# Clock_Distribution.net
KiCad netlist of a schematic drawn in Altium Designer
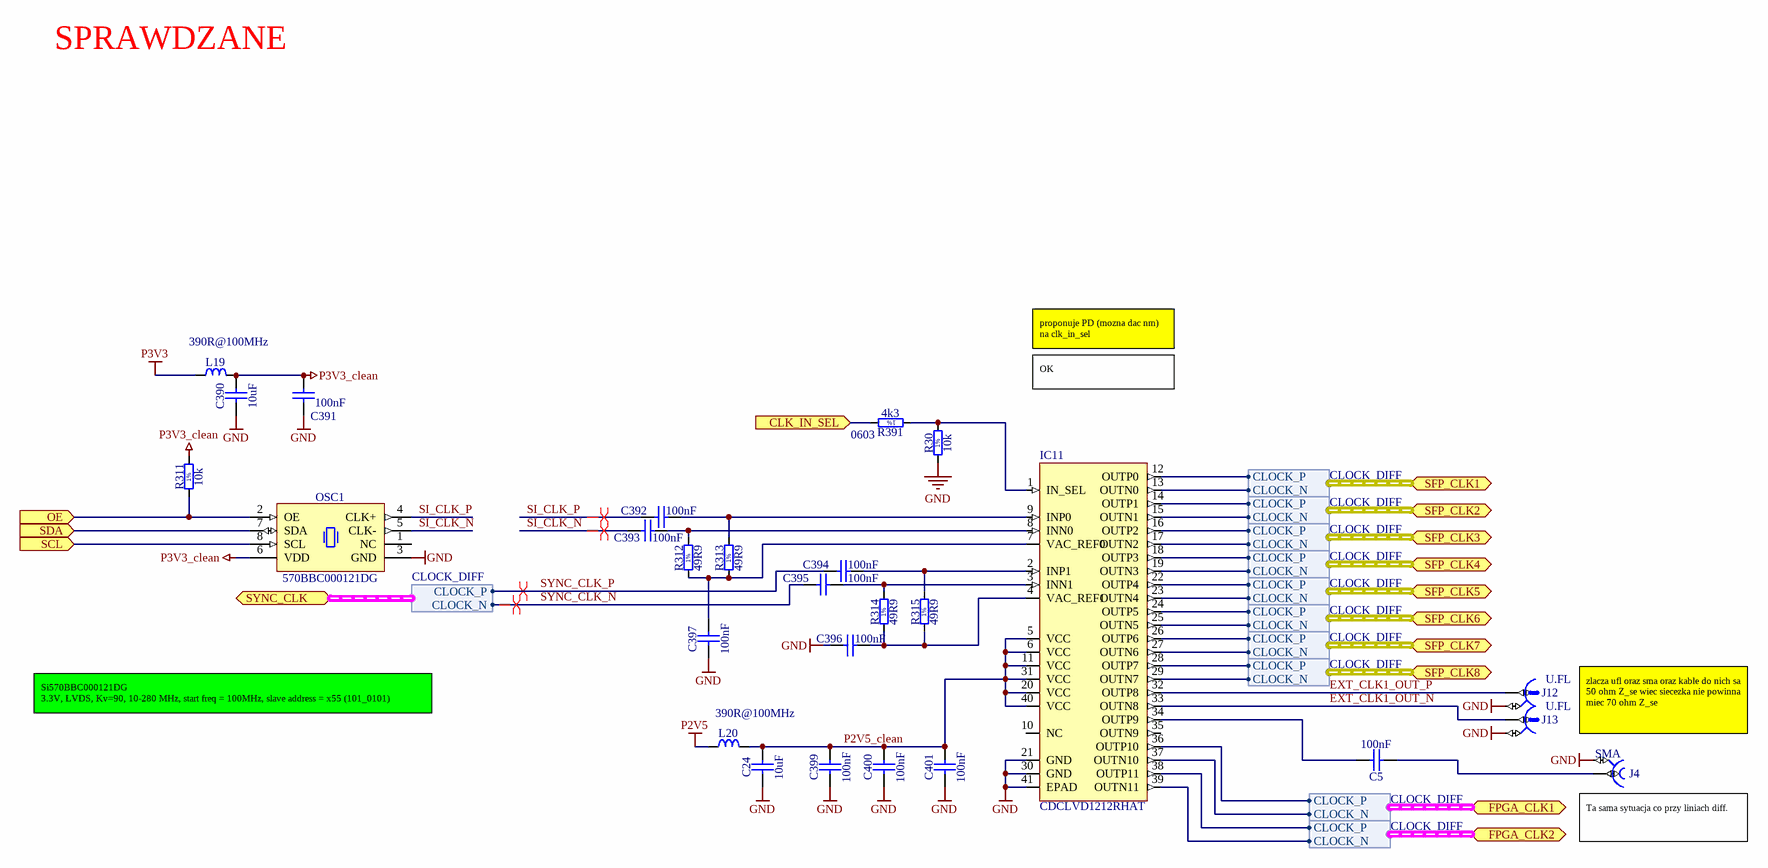
[diagram p0: Clock_Distribution.SchDoc]

(export (version "E")
  (design (tool "Eeschema 10.0.6"))
  (components
    (comp (ref "C5")
      (value "100nF")
      (footprint "CAPC1005X55N")
      (description "Non-polarised capacitor")
      (fields
        (field (name "PART NUMBER") "CC0402_100NF_16V_10%_X7R")
        (field (name "VOLTAGE") "16V")
        (field (name "AUTHOR") "CERN DEM JLC")
      )
      (libsource (lib "Capacitors") (part "Capacitor - non polarized"))
    )
    (comp (ref "C24")
      (value "10uF")
      (footprint "CAPC2012X135N")
      (description "Non-polarised capacitor")
      (fields
        (field (name "PART NUMBER") "CC0805_10UF_10V_10%_X7R")
        (field (name "VOLTAGE") "10V")
        (field (name "AUTHOR") "CERN DEM JLC")
      )
      (libsource (lib "Capacitors") (part "Capacitor - non polarized"))
    )
    (comp (ref "C390")
      (value "10uF")
      (footprint "CAPC2012X135N")
      (description "Non-polarised capacitor")
      (fields
        (field (name "PART NUMBER") "CC0805_10UF_10V_10%_X7R")
        (field (name "VOLTAGE") "10V")
        (field (name "AUTHOR") "CERN DEM JLC")
      )
      (libsource (lib "Capacitors") (part "Capacitor - non polarized"))
    )
    (comp (ref "C391")
      (value "100nF")
      (footprint "CAPC0603X33N")
      (description "Non-polarised capacitor")
      (fields
        (field (name "PART NUMBER") "CC0201_100NF_6.3V_10%_X5R")
        (field (name "VOLTAGE") "6.3V")
        (field (name "AUTHOR") "CERN DEM JLC")
      )
      (libsource (lib "Capacitors") (part "Capacitor - non polarized"))
    )
    (comp (ref "C392")
      (value "100nF")
      (footprint "CAPC0603X33N")
      (description "Non-polarised capacitor")
      (fields
        (field (name "PART NUMBER") "CC0201_100NF_6.3V_10%_X5R")
        (field (name "VOLTAGE") "6.3V")
        (field (name "AUTHOR") "CERN DEM JLC")
      )
      (libsource (lib "Capacitors") (part "Capacitor - non polarized"))
    )
    (comp (ref "C393")
      (value "100nF")
      (footprint "CAPC0603X33N")
      (description "Non-polarised capacitor")
      (fields
        (field (name "PART NUMBER") "CC0201_100NF_6.3V_10%_X5R")
        (field (name "VOLTAGE") "6.3V")
        (field (name "AUTHOR") "CERN DEM JLC")
      )
      (libsource (lib "Capacitors") (part "Capacitor - non polarized"))
    )
    (comp (ref "C394")
      (value "100nF")
      (footprint "CAPC0603X33N")
      (description "Non-polarised capacitor")
      (fields
        (field (name "PART NUMBER") "CC0201_100NF_6.3V_10%_X5R")
        (field (name "VOLTAGE") "6.3V")
        (field (name "AUTHOR") "CERN DEM JLC")
      )
      (libsource (lib "Capacitors") (part "Capacitor - non polarized"))
    )
    (comp (ref "C395")
      (value "100nF")
      (footprint "CAPC0603X33N")
      (description "Non-polarised capacitor")
      (fields
        (field (name "PART NUMBER") "CC0201_100NF_6.3V_10%_X5R")
        (field (name "VOLTAGE") "6.3V")
        (field (name "AUTHOR") "CERN DEM JLC")
      )
      (libsource (lib "Capacitors") (part "Capacitor - non polarized"))
    )
    (comp (ref "C396")
      (value "100nF")
      (footprint "CAPC0603X33N")
      (description "Non-polarised capacitor")
      (fields
        (field (name "PART NUMBER") "CC0201_100NF_6.3V_10%_X5R")
        (field (name "VOLTAGE") "6.3V")
        (field (name "AUTHOR") "CERN DEM JLC")
      )
      (libsource (lib "Capacitors") (part "Capacitor - non polarized"))
    )
    (comp (ref "C397")
      (value "100nF")
      (footprint "CAPC0603X33N")
      (description "Non-polarised capacitor")
      (fields
        (field (name "PART NUMBER") "CC0201_100NF_6.3V_10%_X5R")
        (field (name "VOLTAGE") "6.3V")
        (field (name "AUTHOR") "CERN DEM JLC")
      )
      (libsource (lib "Capacitors") (part "Capacitor - non polarized"))
    )
    (comp (ref "C399")
      (value "100nF")
      (footprint "CAPC0603X33N")
      (description "Non-polarised capacitor")
      (fields
        (field (name "PART NUMBER") "CC0201_100NF_6.3V_10%_X5R")
        (field (name "VOLTAGE") "6.3V")
        (field (name "AUTHOR") "CERN DEM JLC")
      )
      (libsource (lib "Capacitors") (part "Capacitor - non polarized"))
    )
    (comp (ref "C400")
      (value "100nF")
      (footprint "CAPC0603X33N")
      (description "Non-polarised capacitor")
      (fields
        (field (name "PART NUMBER") "CC0201_100NF_6.3V_10%_X5R")
        (field (name "VOLTAGE") "6.3V")
        (field (name "AUTHOR") "CERN DEM JLC")
      )
      (libsource (lib "Capacitors") (part "Capacitor - non polarized"))
    )
    (comp (ref "C401")
      (value "100nF")
      (footprint "CAPC0603X33N")
      (description "Non-polarised capacitor")
      (fields
        (field (name "PART NUMBER") "CC0201_100NF_6.3V_10%_X5R")
        (field (name "VOLTAGE") "6.3V")
        (field (name "AUTHOR") "CERN DEM JLC")
      )
      (libsource (lib "Capacitors") (part "Capacitor - non polarized"))
    )
    (comp (ref "IC11")
      (value "CDCLVD1212RHAT")
      (footprint "QFN50P600-40")
      (description "Low Jitter, 2-Input Selectable 1:12 Universal-to-LVDS Buffer")
      (libsource (lib "LIBRARY_SCH") (part "CLOCK_CDCLVD1212"))
    )
    (comp (ref "J4")
      (value "SMA")
      (footprint "HUBER-SUHNER_85 SMA-50-0-101/111 NE")
      (fields
        (field (name "PART NUMBER") "HUBER-SUHNER_85_SMA-50-0-101/111_NE")
        (field (name "MANUFACTURER") "HUBER+SUHNER")
        (field (name "MANUFACTURER PART NUMBER") "85_SMA-50-0-101/111_NE")
        (field (name "AUTHOR") "CERN DEM JLC")
      )
      (libsource (lib "Connectors") (part "Coax_1Female_1Shield"))
    )
    (comp (ref "J12")
      (value "U.FL")
      (footprint "HIROSE_U.FL-R-SMT-1(10)")
      (fields
        (field (name "PART NUMBER") "HIROSE_U.FL-R-SMT-1(10)")
        (field (name "MANUFACTURER") "HIROSE (HRS)")
        (field (name "MANUFACTURER PART NUMBER") "U.FL-R-SMT-1(10)")
        (field (name "AUTHOR") "CERN DEM JLC")
      )
      (libsource (lib "Connectors") (part "Coax_1Male_1Shield"))
    )
    (comp (ref "J13")
      (value "U.FL")
      (footprint "HIROSE_U.FL-R-SMT-1(10)")
      (fields
        (field (name "PART NUMBER") "HIROSE_U.FL-R-SMT-1(10)")
        (field (name "MANUFACTURER") "HIROSE (HRS)")
        (field (name "MANUFACTURER PART NUMBER") "U.FL-R-SMT-1(10)")
        (field (name "AUTHOR") "CERN DEM JLC")
      )
      (libsource (lib "Connectors") (part "Coax_1Male_1Shield"))
    )
    (comp (ref "L19")
      (value "390R@100MHz")
      (footprint "INDC1608X95N")
      (description "Inductor")
      (fields
        (field (name "PART NUMBER") "IND0603_TDK_MPZ1608R391A")
        (field (name "POWER") "1.2A")
        (field (name "AUTHOR") "CERN DEM JLC")
      )
      (libsource (lib "Inductors & Transformers") (part "Inductor"))
    )
    (comp (ref "L20")
      (value "390R@100MHz")
      (footprint "INDC1608X95N")
      (description "Inductor")
      (fields
        (field (name "PART NUMBER") "IND0603_TDK_MPZ1608R391A")
        (field (name "POWER") "1.2A")
        (field (name "AUTHOR") "CERN DEM JLC")
      )
      (libsource (lib "Inductors & Transformers") (part "Inductor"))
    )
    (comp (ref "OSC1")
      (value "570BBC000121DG")
      (footprint "OSC_SILICON-LAB_SI570")
      (description "Any-Rate I2C Programmable XO Oscillator Si570 Serie")
      (fields
        (field (name "PART NUMBER") "OSC_10-280MHZ_SILICON-LAB_Si570BBC000121DG")
        (field (name "MANUFACTURER") "SILICON LABS")
        (field (name "AUTHOR") "CERN DEM JLC")
      )
      (libsource (lib "ICs And Semiconductors") (part "Oscillator SILICON-LAB_Si570"))
    )
    (comp (ref "R30")
      (value "10k")
      (footprint "RESC1005X40N")
      (description "Resistor - 1%")
      (fields
        (field (name "PART NUMBER") "R0402_10K_1%_0.0625W_100PPM")
        (field (name "POWER") "0.0625W")
        (field (name "AUTHOR") "CERN DEM JLC")
      )
      (libsource (lib "Resistors") (part "Resistor - 1%"))
    )
    (comp (ref "R311")
      (value "10k")
      (footprint "RESC1005X40N")
      (description "Resistor - 1%")
      (fields
        (field (name "PART NUMBER") "R0402_10K_1%_0.0625W_100PPM")
        (field (name "POWER") "0.0625W")
        (field (name "AUTHOR") "CERN DEM JLC")
      )
      (libsource (lib "Resistors") (part "Resistor - 1%"))
    )
    (comp (ref "R312")
      (value "49R9")
      (footprint "RESC1005X40N")
      (description "Resistor - 1%")
      (fields
        (field (name "PART NUMBER") "R0402_49R9_1%_0.0625W_100PPM")
        (field (name "POWER") "0.0625W")
        (field (name "AUTHOR") "CERN DEM JLC")
      )
      (libsource (lib "Resistors") (part "Resistor - 1%"))
    )
    (comp (ref "R313")
      (value "49R9")
      (footprint "RESC1005X40N")
      (description "Resistor - 1%")
      (fields
        (field (name "PART NUMBER") "R0402_49R9_1%_0.0625W_100PPM")
        (field (name "POWER") "0.0625W")
        (field (name "AUTHOR") "CERN DEM JLC")
      )
      (libsource (lib "Resistors") (part "Resistor - 1%"))
    )
    (comp (ref "R314")
      (value "49R9")
      (footprint "RESC1005X40N")
      (description "Resistor - 1%")
      (fields
        (field (name "PART NUMBER") "R0402_49R9_1%_0.0625W_100PPM")
        (field (name "POWER") "0.0625W")
        (field (name "AUTHOR") "CERN DEM JLC")
      )
      (libsource (lib "Resistors") (part "Resistor - 1%"))
    )
    (comp (ref "R315")
      (value "49R9")
      (footprint "RESC1005X40N")
      (description "Resistor - 1%")
      (fields
        (field (name "PART NUMBER") "R0402_49R9_1%_0.0625W_100PPM")
        (field (name "POWER") "0.0625W")
        (field (name "AUTHOR") "CERN DEM JLC")
      )
      (libsource (lib "Resistors") (part "Resistor - 1%"))
    )
    (comp (ref "R391")
      (value "4k3")
      (footprint "RESC1608X55N")
      (description "Resistor - 1%")
      (fields
        (field (name "PART NUMBER") "R0603_4K3_1%_0.1W_100PPM")
        (field (name "POWER") "0.1W")
        (field (name "CASE") "0603")
        (field (name "AUTHOR") "CERN DEM JLC")
      )
      (libsource (lib "Resistors") (part "Resistor - 1%"))
    )
  )
  (nets
    (net (code "3") (name "/CLK_IN_SEL") (class "Default")
      (node (ref "R391") (pin "2") (pinfunction "2_2") (pintype "passive"))
    )
    (net (code "4") (name "/EXT_CLK1_OUT_N") (class "Default")
      (node (ref "IC11") (pin "33") (pinfunction "OUTN8_33") (pintype "output"))
      (node (ref "J13") (pin "1") (pinfunction "1_1") (pintype "bidirectional"))
    )
    (net (code "5") (name "/EXT_CLK1_OUT_P") (class "Default")
      (node (ref "IC11") (pin "32") (pinfunction "OUTP8_32") (pintype "output"))
      (node (ref "J12") (pin "1") (pinfunction "1_1") (pintype "bidirectional"))
    )
    (net (code "6") (name "/OE") (class "Default")
      (node (ref "OSC1") (pin "2") (pinfunction "OE_2") (pintype "input"))
      (node (ref "R311") (pin "1") (pinfunction "1_1") (pintype "passive"))
    )
    (net (code "7") (name "/P2V5_clean") (class "Default")
      (node (ref "C24") (pin "2") (pinfunction "2_2") (pintype "passive"))
      (node (ref "C399") (pin "2") (pinfunction "2_2") (pintype "passive"))
      (node (ref "C400") (pin "2") (pinfunction "2_2") (pintype "passive"))
      (node (ref "C401") (pin "2") (pinfunction "2_2") (pintype "passive"))
      (node (ref "IC11") (pin "11") (pinfunction "VCC_11") (pintype "power_in"))
      (node (ref "IC11") (pin "20") (pinfunction "VCC_20") (pintype "power_in"))
      (node (ref "IC11") (pin "31") (pinfunction "VCC_31") (pintype "power_in"))
      (node (ref "IC11") (pin "40") (pinfunction "VCC_40") (pintype "power_in"))
      (node (ref "IC11") (pin "5") (pinfunction "VCC_5") (pintype "power_in"))
      (node (ref "IC11") (pin "6") (pinfunction "VCC_6") (pintype "power_in"))
      (node (ref "L20") (pin "2") (pinfunction "2_2") (pintype "passive"))
    )
    (net (code "8") (name "/SCL") (class "Default")
      (node (ref "OSC1") (pin "8") (pinfunction "SCL_8") (pintype "input"))
    )
    (net (code "9") (name "/SDA") (class "Default")
      (node (ref "OSC1") (pin "7") (pinfunction "SDA_7") (pintype "bidirectional"))
    )
    (net (code "11") (name "/SI_CLK_N") (class "Default")
      (node (ref "C393") (pin "2") (pinfunction "2_2") (pintype "passive"))
      (node (ref "OSC1") (pin "5") (pinfunction "CLK-_5") (pintype "output"))
    )
    (net (code "12") (name "/SI_CLK_P") (class "Default")
      (node (ref "C392") (pin "2") (pinfunction "2_2") (pintype "passive"))
      (node (ref "OSC1") (pin "4") (pinfunction "CLK+_4") (pintype "output"))
    )
    (net (code "13") (name "/SYNC_CLK_N") (class "Default")
      (node (ref "C395") (pin "2") (pinfunction "2_2") (pintype "passive"))
    )
    (net (code "14") (name "/SYNC_CLK_P") (class "Default")
      (node (ref "C394") (pin "2") (pinfunction "2_2") (pintype "passive"))
    )
    (net (code "16") (name "GND") (class "Default")
      (node (ref "C24") (pin "1") (pinfunction "1_1") (pintype "passive"))
      (node (ref "C390") (pin "1") (pinfunction "1_1") (pintype "passive"))
      (node (ref "C391") (pin "1") (pinfunction "1_1") (pintype "passive"))
      (node (ref "C396") (pin "1") (pinfunction "1_1") (pintype "passive"))
      (node (ref "C397") (pin "1") (pinfunction "1_1") (pintype "passive"))
      (node (ref "C399") (pin "1") (pinfunction "1_1") (pintype "passive"))
      (node (ref "C400") (pin "1") (pinfunction "1_1") (pintype "passive"))
      (node (ref "C401") (pin "1") (pinfunction "1_1") (pintype "passive"))
      (node (ref "IC11") (pin "21") (pinfunction "GND_21") (pintype "power_in"))
      (node (ref "IC11") (pin "30") (pinfunction "GND_30") (pintype "power_in"))
      (node (ref "IC11") (pin "41") (pinfunction "EPAD_41") (pintype "power_in"))
      (node (ref "J12") (pin "2") (pinfunction "2_2") (pintype "bidirectional"))
      (node (ref "J13") (pin "2") (pinfunction "2_2") (pintype "bidirectional"))
      (node (ref "J4") (pin "2") (pinfunction "2_2") (pintype "bidirectional"))
      (node (ref "OSC1") (pin "3") (pinfunction "GND_3") (pintype "power_in"))
      (node (ref "R30") (pin "1") (pinfunction "1_1") (pintype "passive"))
    )
    (net (code "17") (name "Net-(C5-Pad2)") (class "Default")
      (node (ref "C5") (pin "2") (pinfunction "2_2") (pintype "passive"))
      (node (ref "J4") (pin "1") (pinfunction "1_1") (pintype "bidirectional"))
    )
    (net (code "18") (name "Net-(IC11-INN0)") (class "Default")
      (node (ref "C393") (pin "1") (pinfunction "1_1") (pintype "passive"))
      (node (ref "IC11") (pin "8") (pinfunction "INN0_8") (pintype "input"))
      (node (ref "R312") (pin "2") (pinfunction "2_2") (pintype "passive"))
    )
    (net (code "19") (name "Net-(IC11-INN1)") (class "Default")
      (node (ref "C395") (pin "1") (pinfunction "1_1") (pintype "passive"))
      (node (ref "IC11") (pin "3") (pinfunction "INN1_3") (pintype "input"))
      (node (ref "R314") (pin "2") (pinfunction "2_2") (pintype "passive"))
    )
    (net (code "20") (name "Net-(IC11-INP0)") (class "Default")
      (node (ref "C392") (pin "1") (pinfunction "1_1") (pintype "passive"))
      (node (ref "IC11") (pin "9") (pinfunction "INP0_9") (pintype "input"))
      (node (ref "R313") (pin "2") (pinfunction "2_2") (pintype "passive"))
    )
    (net (code "21") (name "Net-(IC11-INP1)") (class "Default")
      (node (ref "C394") (pin "1") (pinfunction "1_1") (pintype "passive"))
      (node (ref "IC11") (pin "2") (pinfunction "INP1_2") (pintype "input"))
      (node (ref "R315") (pin "2") (pinfunction "2_2") (pintype "passive"))
    )
    (net (code "22") (name "Net-(IC11-IN_SEL)") (class "Default")
      (node (ref "IC11") (pin "1") (pinfunction "IN_SEL_1") (pintype "input"))
      (node (ref "R30") (pin "2") (pinfunction "2_2") (pintype "passive"))
      (node (ref "R391") (pin "1") (pinfunction "1_1") (pintype "passive"))
    )
    (net (code "23") (name "Net-(IC11-OUTP9)") (class "Default")
      (node (ref "C5") (pin "1") (pinfunction "1_1") (pintype "passive"))
      (node (ref "IC11") (pin "34") (pinfunction "OUTP9_34") (pintype "output"))
    )
    (net (code "24") (name "Net-(IC11-VAC_REF0)") (class "Default")
      (node (ref "C397") (pin "2") (pinfunction "2_2") (pintype "passive"))
      (node (ref "IC11") (pin "7") (pinfunction "VAC_REF0_7") (pintype "power_in"))
      (node (ref "R312") (pin "1") (pinfunction "1_1") (pintype "passive"))
      (node (ref "R313") (pin "1") (pinfunction "1_1") (pintype "passive"))
    )
    (net (code "25") (name "Net-(IC11-VAC_REF1)") (class "Default")
      (node (ref "C396") (pin "2") (pinfunction "2_2") (pintype "passive"))
      (node (ref "IC11") (pin "4") (pinfunction "VAC_REF1_4") (pintype "power_in"))
      (node (ref "R314") (pin "1") (pinfunction "1_1") (pintype "passive"))
      (node (ref "R315") (pin "1") (pinfunction "1_1") (pintype "passive"))
    )
    (net (code "26") (name "P2V5") (class "Default")
      (node (ref "L20") (pin "1") (pinfunction "1_1") (pintype "passive"))
    )
    (net (code "27") (name "P3V3") (class "Default")
      (node (ref "L19") (pin "1") (pinfunction "1_1") (pintype "passive"))
    )
    (net (code "28") (name "P3V3_clean") (class "Default")
      (node (ref "C390") (pin "2") (pinfunction "2_2") (pintype "passive"))
      (node (ref "C391") (pin "2") (pinfunction "2_2") (pintype "passive"))
      (node (ref "L19") (pin "2") (pinfunction "2_2") (pintype "passive"))
      (node (ref "OSC1") (pin "6") (pinfunction "VDD_6") (pintype "power_in"))
      (node (ref "R311") (pin "2") (pinfunction "2_2") (pintype "passive"))
    )
    (net (code "29") (name "unconnected-(IC11-NC-Pad10)") (class "Default")
      (node (ref "IC11") (pin "10") (pinfunction "NC_10") (pintype "passive"))
    )
    (net (code "30") (name "unconnected-(IC11-OUTN0-Pad13)") (class "Default")
      (node (ref "IC11") (pin "13") (pinfunction "OUTN0_13") (pintype "output"))
    )
    (net (code "31") (name "unconnected-(IC11-OUTN1-Pad15)") (class "Default")
      (node (ref "IC11") (pin "15") (pinfunction "OUTN1_15") (pintype "output"))
    )
    (net (code "32") (name "unconnected-(IC11-OUTN2-Pad17)") (class "Default")
      (node (ref "IC11") (pin "17") (pinfunction "OUTN2_17") (pintype "output"))
    )
    (net (code "33") (name "unconnected-(IC11-OUTN3-Pad19)") (class "Default")
      (node (ref "IC11") (pin "19") (pinfunction "OUTN3_19") (pintype "output"))
    )
    (net (code "34") (name "unconnected-(IC11-OUTN4-Pad23)") (class "Default")
      (node (ref "IC11") (pin "23") (pinfunction "OUTN4_23") (pintype "output"))
    )
    (net (code "35") (name "unconnected-(IC11-OUTN5-Pad25)") (class "Default")
      (node (ref "IC11") (pin "25") (pinfunction "OUTN5_25") (pintype "output"))
    )
    (net (code "36") (name "unconnected-(IC11-OUTN6-Pad27)") (class "Default")
      (node (ref "IC11") (pin "27") (pinfunction "OUTN6_27") (pintype "output"))
    )
    (net (code "37") (name "unconnected-(IC11-OUTN7-Pad29)") (class "Default")
      (node (ref "IC11") (pin "29") (pinfunction "OUTN7_29") (pintype "output"))
    )
    (net (code "38") (name "unconnected-(IC11-OUTN9-Pad35)") (class "Default")
      (node (ref "IC11") (pin "35") (pinfunction "OUTN9_35") (pintype "output"))
    )
    (net (code "39") (name "unconnected-(IC11-OUTN10-Pad37)") (class "Default")
      (node (ref "IC11") (pin "37") (pinfunction "OUTN10_37") (pintype "output"))
    )
    (net (code "40") (name "unconnected-(IC11-OUTN11-Pad39)") (class "Default")
      (node (ref "IC11") (pin "39") (pinfunction "OUTN11_39") (pintype "output"))
    )
    (net (code "41") (name "unconnected-(IC11-OUTP0-Pad12)") (class "Default")
      (node (ref "IC11") (pin "12") (pinfunction "OUTP0_12") (pintype "output"))
    )
    (net (code "42") (name "unconnected-(IC11-OUTP1-Pad14)") (class "Default")
      (node (ref "IC11") (pin "14") (pinfunction "OUTP1_14") (pintype "output"))
    )
    (net (code "43") (name "unconnected-(IC11-OUTP2-Pad16)") (class "Default")
      (node (ref "IC11") (pin "16") (pinfunction "OUTP2_16") (pintype "output"))
    )
    (net (code "44") (name "unconnected-(IC11-OUTP3-Pad18)") (class "Default")
      (node (ref "IC11") (pin "18") (pinfunction "OUTP3_18") (pintype "output"))
    )
    (net (code "45") (name "unconnected-(IC11-OUTP4-Pad22)") (class "Default")
      (node (ref "IC11") (pin "22") (pinfunction "OUTP4_22") (pintype "output"))
    )
    (net (code "46") (name "unconnected-(IC11-OUTP5-Pad24)") (class "Default")
      (node (ref "IC11") (pin "24") (pinfunction "OUTP5_24") (pintype "output"))
    )
    (net (code "47") (name "unconnected-(IC11-OUTP6-Pad26)") (class "Default")
      (node (ref "IC11") (pin "26") (pinfunction "OUTP6_26") (pintype "output"))
    )
    (net (code "48") (name "unconnected-(IC11-OUTP7-Pad28)") (class "Default")
      (node (ref "IC11") (pin "28") (pinfunction "OUTP7_28") (pintype "output"))
    )
    (net (code "49") (name "unconnected-(IC11-OUTP10-Pad36)") (class "Default")
      (node (ref "IC11") (pin "36") (pinfunction "OUTP10_36") (pintype "output"))
    )
    (net (code "50") (name "unconnected-(IC11-OUTP11-Pad38)") (class "Default")
      (node (ref "IC11") (pin "38") (pinfunction "OUTP11_38") (pintype "output"))
    )
    (net (code "51") (name "unconnected-(OSC1-NC-Pad1)") (class "Default")
      (node (ref "OSC1") (pin "1") (pinfunction "NC_1") (pintype "passive"))
    )
  )
)
